# DiffAmp_K-10.net
KiCad netlist of a schematic drawn in Altium Designer
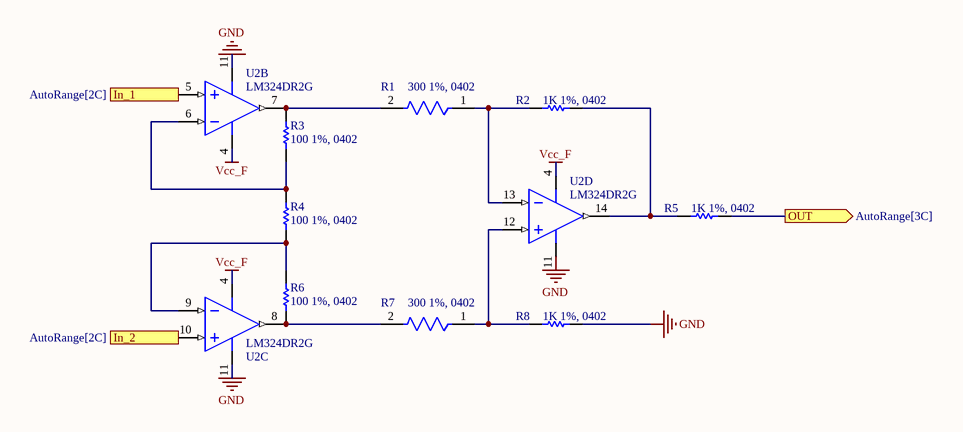
[diagram p0: DiffAmp_K-10.SchDoc]

(export (version "E")
  (design (tool "Eeschema 10.0.6"))
  (components
    (comp (ref "R1")
      (value "300 1%, 0402")
      (footprint "FP-ERJ2RK-IPC_A")
      (description "RES SMD 300 OHM 1% 1/10W 0402")
      (fields (field (name "TOLERANCE") "1%"))
      (libsource (lib "Altium Content Vault") (part "1029c3af85768c4190bb7ad29bc67b5"))
    )
    (comp (ref "R2")
      (value "1K 1%, 0402")
      (footprint "RESC1005X40X25NL05T05")
      (description "Chip Resistor, 1 KOhm, +/- 1%, 100 mW, -55 to 155 degC, 0402 (1005 Metric), RoHS, Tape and Reel")
      (fields (field (name "PARTNUMBER") "ERJ-2RKF1001X") (field (name "MANUFACTURER") "Basic Passives"))
      (libsource (lib "Altium Content Vault") (part "RES-2"))
    )
    (comp (ref "R3")
      (value "100 1%, 0402")
      (footprint "RESC1005X40X25LL05T05")
      (description "Chip Resistor, 100 Ohm, +/- 1%, 100 mW, -55 to 155 degC, 0402 (1005 Metric), RoHS, Tape and Reel")
      (fields (field (name "MANUFACTURER") "Basic Passives") (field (name "TOLERANCE") "1%"))
      (libsource (lib "Altium Content Vault") (part "RES-2"))
    )
    (comp (ref "R4")
      (value "100 1%, 0402")
      (footprint "RESC1005X40X25LL05T05")
      (description "Chip Resistor, 100 Ohm, +/- 1%, 100 mW, -55 to 155 degC, 0402 (1005 Metric), RoHS, Tape and Reel")
      (fields (field (name "MANUFACTURER") "Basic Passives") (field (name "TOLERANCE") "1%"))
      (libsource (lib "Altium Content Vault") (part "RES-2"))
    )
    (comp (ref "R5")
      (value "1K 1%, 0402")
      (footprint "RESC1005X40X25NL05T05")
      (description "Chip Resistor, 1 KOhm, +/- 1%, 100 mW, -55 to 155 degC, 0402 (1005 Metric), RoHS, Tape and Reel")
      (fields (field (name "PARTNUMBER") "ERJ-2RKF1001X") (field (name "MANUFACTURER") "Basic Passives"))
      (libsource (lib "Altium Content Vault") (part "RES-2"))
    )
    (comp (ref "R6")
      (value "100 1%, 0402")
      (footprint "RESC1005X40X25LL05T05")
      (description "Chip Resistor, 100 Ohm, +/- 1%, 100 mW, -55 to 155 degC, 0402 (1005 Metric), RoHS, Tape and Reel")
      (fields (field (name "MANUFACTURER") "Basic Passives") (field (name "TOLERANCE") "1%"))
      (libsource (lib "Altium Content Vault") (part "RES-2"))
    )
    (comp (ref "R7")
      (value "300 1%, 0402")
      (footprint "FP-ERJ2RK-IPC_A")
      (description "RES SMD 300 OHM 1% 1/10W 0402")
      (fields (field (name "TOLERANCE") "1%"))
      (libsource (lib "Altium Content Vault") (part "1029c3af85768c4190bb7ad29bc67b5"))
    )
    (comp (ref "R8")
      (value "1K 1%, 0402")
      (footprint "RESC1005X40X25NL05T05")
      (description "Chip Resistor, 1 KOhm, +/- 1%, 100 mW, -55 to 155 degC, 0402 (1005 Metric), RoHS, Tape and Reel")
      (fields (field (name "PARTNUMBER") "ERJ-2RKF1001X") (field (name "MANUFACTURER") "Basic Passives"))
      (libsource (lib "Altium Content Vault") (part "RES-2"))
    )
    (comp (ref "U2")
      (value "LM324DR2G")
      (footprint "ONSC-SOIC-14-751A-03_V")
      (fields (field (name "MANUFACTURER") "On Semiconductor"))
      (libsource (lib "Altium Content Vault") (part "ONSC-LM224_324_2902_NCV2902-14"))
    )
  )
  (nets
    (net (code "1") (name "/In_1") (class "Default")
      (node (ref "U2") (pin "5") (pinfunction "IN2+_5") (pintype "input"))
    )
    (net (code "2") (name "/In_2") (class "Default")
      (node (ref "U2") (pin "10") (pinfunction "IN3+_10") (pintype "input"))
    )
    (net (code "3") (name "/OUT") (class "Default")
      (node (ref "R5") (pin "2") (pinfunction "2_2") (pintype "passive"))
    )
    (net (code "4") (name "GND") (class "Default")
      (node (ref "R8") (pin "2") (pinfunction "2_2") (pintype "passive"))
      (node (ref "U2") (pin "11") (pinfunction "VEE/GND_11") (pintype "power_in"))
    )
    (net (code "5") (name "Net-(U2B-IN2-)") (class "Default")
      (node (ref "R3") (pin "1") (pinfunction "1_1") (pintype "passive"))
      (node (ref "R4") (pin "2") (pinfunction "2_2") (pintype "passive"))
      (node (ref "U2") (pin "6") (pinfunction "IN2-_6") (pintype "input"))
    )
    (net (code "6") (name "Net-(U2B-OUT2)") (class "Default")
      (node (ref "R1") (pin "2") (pinfunction "2_2") (pintype "passive"))
      (node (ref "R3") (pin "2") (pinfunction "2_2") (pintype "passive"))
      (node (ref "U2") (pin "7") (pinfunction "OUT2_7") (pintype "output"))
    )
    (net (code "7") (name "Net-(U2C-IN3-)") (class "Default")
      (node (ref "R4") (pin "1") (pinfunction "1_1") (pintype "passive"))
      (node (ref "R6") (pin "2") (pinfunction "2_2") (pintype "passive"))
      (node (ref "U2") (pin "9") (pinfunction "IN3-_9") (pintype "input"))
    )
    (net (code "8") (name "Net-(U2C-OUT3)") (class "Default")
      (node (ref "R6") (pin "1") (pinfunction "1_1") (pintype "passive"))
      (node (ref "R7") (pin "2") (pinfunction "2_2") (pintype "passive"))
      (node (ref "U2") (pin "8") (pinfunction "OUT3_8") (pintype "output"))
    )
    (net (code "9") (name "Net-(U2D-IN4+)") (class "Default")
      (node (ref "R7") (pin "1") (pinfunction "1_1") (pintype "passive"))
      (node (ref "R8") (pin "1") (pinfunction "1_1") (pintype "passive"))
      (node (ref "U2") (pin "12") (pinfunction "IN4+_12") (pintype "input"))
    )
    (net (code "10") (name "Net-(U2D-IN4-)") (class "Default")
      (node (ref "R1") (pin "1") (pinfunction "1_1") (pintype "passive"))
      (node (ref "R2") (pin "1") (pinfunction "1_1") (pintype "passive"))
      (node (ref "U2") (pin "13") (pinfunction "IN4-_13") (pintype "input"))
    )
    (net (code "11") (name "Net-(U2D-OUT4)") (class "Default")
      (node (ref "R2") (pin "2") (pinfunction "2_2") (pintype "passive"))
      (node (ref "R5") (pin "1") (pinfunction "1_1") (pintype "passive"))
      (node (ref "U2") (pin "14") (pinfunction "OUT4_14") (pintype "output"))
    )
    (net (code "12") (name "Vcc_F") (class "Default")
      (node (ref "U2") (pin "4") (pinfunction "VCC_4") (pintype "power_in"))
    )
    (net (code "13") (name "unconnected-(U2D-VEE{slash}GND-Pad11)") (class "Default")
      (node (ref "U2") (pin "11") (pinfunction "VEE/GND_11") (pintype "power_in"))
    )
  )
)
